# ExtensionConnector.net
KiCad netlist of a schematic drawn in Altium Designer
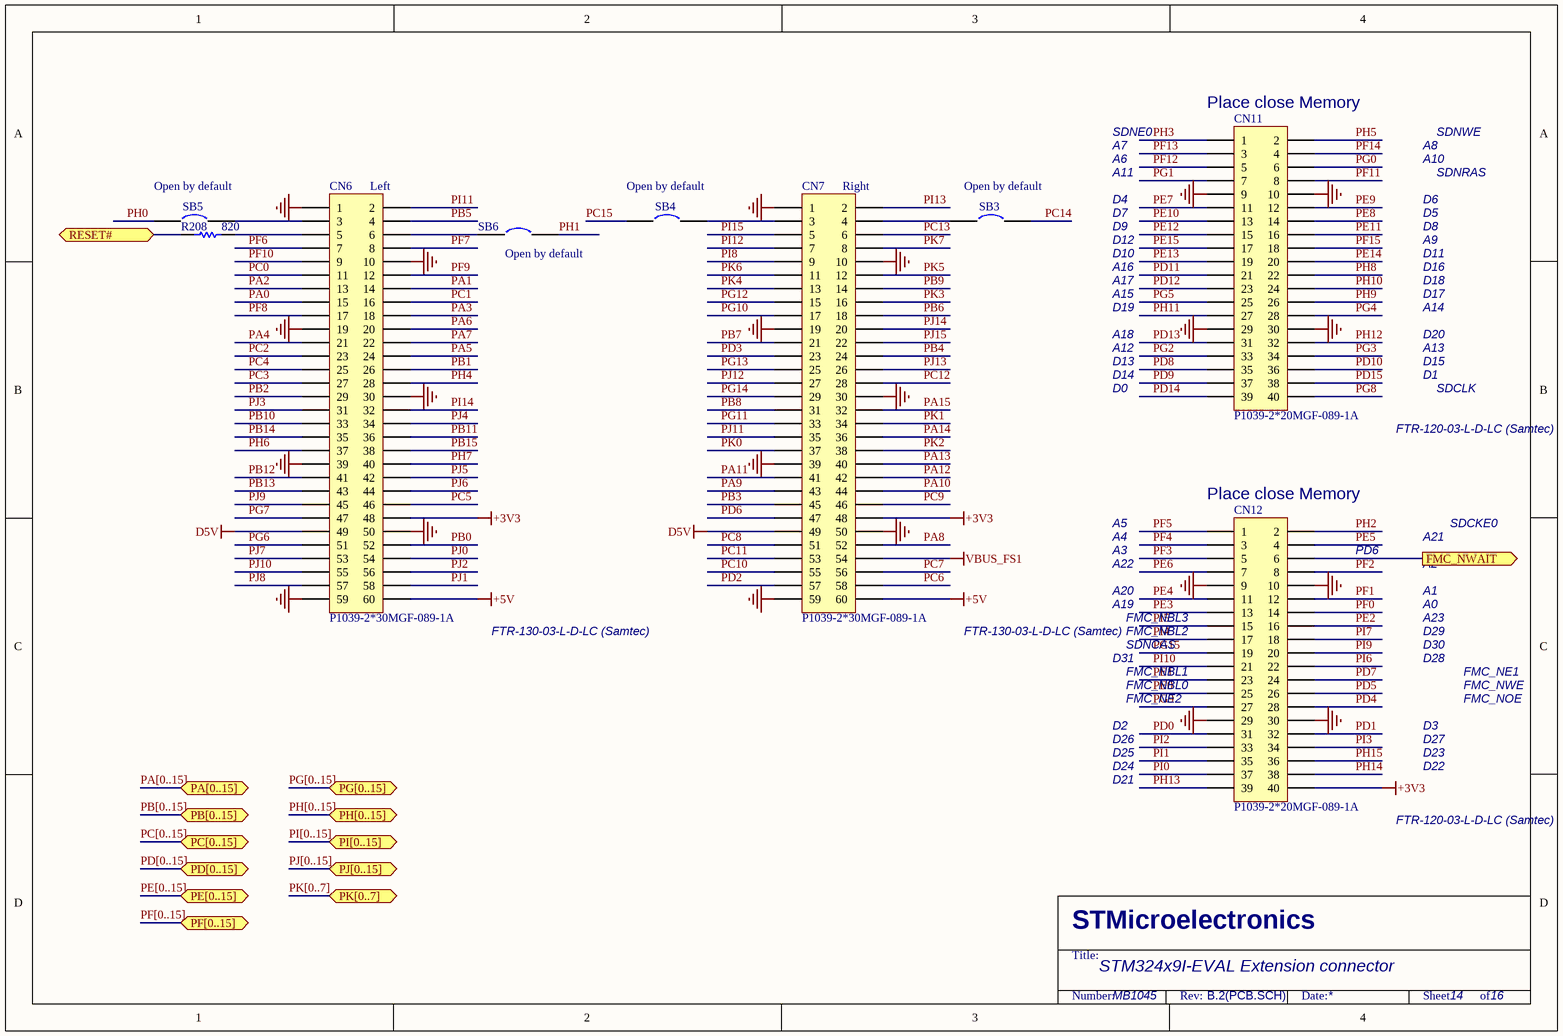
[diagram p0: ExtensionConnector.SchDoc]

(export (version "E")
  (design (tool "Eeschema 10.0.6"))
  (components
    (comp (ref "CN6")
      (value "P1039-2*30MGF-089-1A")
      (footprint "FTR-130-53-L-D-LC")
      (description "Header, 40-Pin, Dual row")
      (fields (field (name "PUBLISHER") "Altium Limited"))
      (libsource (lib "mb1045") (part "FTR-130-53-L-D-LC"))
    )
    (comp (ref "CN7")
      (value "P1039-2*30MGF-089-1A")
      (footprint "FTR-130-53-L-D-LC")
      (description "Header, 40-Pin, Dual row")
      (fields (field (name "PUBLISHER") "Altium Limited"))
      (libsource (lib "mb1045") (part "FTR-130-53-L-D-LC"))
    )
    (comp (ref "CN11")
      (value "P1039-2*20MGF-089-1A")
      (footprint "FTR-120-53-L-D-LC")
      (description "Header, 20-Pin, Dual row")
      (fields (field (name "PUBLISHER") "Altium Limited"))
      (libsource (lib "mb1045") (part "FTR-120-53-L-D-LC"))
    )
    (comp (ref "CN12")
      (value "P1039-2*20MGF-089-1A")
      (footprint "FTR-120-53-L-D-LC")
      (description "Header, 20-Pin, Dual row")
      (fields (field (name "PUBLISHER") "Altium Limited"))
      (libsource (lib "mb1045") (part "FTR-120-53-L-D-LC"))
    )
    (comp (ref "R208")
      (value "820")
      (footprint "0603R")
      (description "Resistor")
      (fields (field (name "PUBLISHER") "Altium Limited"))
      (libsource (lib "Miscellaneous Devices") (part "res1"))
    )
    (comp (ref "SB3")
      (value "~")
      (footprint "JP2_SMD")
      (description "Circuit Breaker")
      (fields (field (name "PUBLISHER") "Altium Limited"))
      (libsource (lib "Miscellaneous Devices") (part "Circuit Breaker"))
    )
    (comp (ref "SB4")
      (value "~")
      (footprint "JP2_SMD")
      (description "Circuit Breaker")
      (fields (field (name "PUBLISHER") "Altium Limited"))
      (libsource (lib "") (part "Circuit Breaker_1"))
    )
    (comp (ref "SB5")
      (value "~")
      (footprint "JP2_SMD")
      (description "Circuit Breaker")
      (fields (field (name "PUBLISHER") "Altium Limited"))
      (libsource (lib "") (part "Circuit Breaker_1"))
    )
    (comp (ref "SB6")
      (value "~")
      (footprint "JP2_SMD")
      (description "Circuit Breaker")
      (fields (field (name "PUBLISHER") "Altium Limited"))
      (libsource (lib "Miscellaneous Devices") (part "Circuit Breaker"))
    )
  )
  (nets
    (net (code "1") (name "+3V3") (class "Default")
      (node (ref "CN12") (pin "40") (pinfunction "40_40") (pintype "passive"))
      (node (ref "CN6") (pin "48") (pinfunction "48_48") (pintype "passive"))
      (node (ref "CN7") (pin "48") (pinfunction "48_48") (pintype "passive"))
    )
    (net (code "2") (name "+5V") (class "Default")
      (node (ref "CN6") (pin "60") (pinfunction "60_60") (pintype "passive"))
      (node (ref "CN7") (pin "60") (pinfunction "60_60") (pintype "passive"))
    )
    (net (code "3") (name "/FMC_NWAIT") (class "Default")
      (node (ref "CN12") (pin "6") (pinfunction "6_6") (pintype "passive"))
    )
    (net (code "4") (name "/PA0") (class "Default")
      (node (ref "CN6") (pin "15") (pinfunction "15_15") (pintype "passive"))
    )
    (net (code "5") (name "/PA1") (class "Default")
      (node (ref "CN6") (pin "14") (pinfunction "14_14") (pintype "passive"))
    )
    (net (code "6") (name "/PA2") (class "Default")
      (node (ref "CN6") (pin "13") (pinfunction "13_13") (pintype "passive"))
    )
    (net (code "7") (name "/PA3") (class "Default")
      (node (ref "CN6") (pin "18") (pinfunction "18_18") (pintype "passive"))
    )
    (net (code "8") (name "/PA4") (class "Default")
      (node (ref "CN6") (pin "21") (pinfunction "21_21") (pintype "passive"))
    )
    (net (code "9") (name "/PA5") (class "Default")
      (node (ref "CN6") (pin "24") (pinfunction "24_24") (pintype "passive"))
    )
    (net (code "10") (name "/PA6") (class "Default")
      (node (ref "CN6") (pin "20") (pinfunction "20_20") (pintype "passive"))
    )
    (net (code "11") (name "/PA7") (class "Default")
      (node (ref "CN6") (pin "22") (pinfunction "22_22") (pintype "passive"))
    )
    (net (code "12") (name "/PA8") (class "Default")
      (node (ref "CN7") (pin "52") (pinfunction "52_52") (pintype "passive"))
    )
    (net (code "13") (name "/PA9") (class "Default")
      (node (ref "CN7") (pin "43") (pinfunction "43_43") (pintype "passive"))
    )
    (net (code "14") (name "/PA10") (class "Default")
      (node (ref "CN7") (pin "44") (pinfunction "44_44") (pintype "passive"))
    )
    (net (code "15") (name "/PA11") (class "Default")
      (node (ref "CN7") (pin "41") (pinfunction "41_41") (pintype "passive"))
    )
    (net (code "16") (name "/PA12") (class "Default")
      (node (ref "CN7") (pin "42") (pinfunction "42_42") (pintype "passive"))
    )
    (net (code "17") (name "/PA13") (class "Default")
      (node (ref "CN7") (pin "40") (pinfunction "40_40") (pintype "passive"))
    )
    (net (code "18") (name "/PA14") (class "Default")
      (node (ref "CN7") (pin "36") (pinfunction "36_36") (pintype "passive"))
    )
    (net (code "19") (name "/PA15") (class "Default")
      (node (ref "CN7") (pin "32") (pinfunction "32_32") (pintype "passive"))
    )
    (net (code "21") (name "/PB0") (class "Default")
      (node (ref "CN6") (pin "52") (pinfunction "52_52") (pintype "passive"))
    )
    (net (code "22") (name "/PB1") (class "Default")
      (node (ref "CN6") (pin "26") (pinfunction "26_26") (pintype "passive"))
    )
    (net (code "23") (name "/PB2") (class "Default")
      (node (ref "CN6") (pin "29") (pinfunction "29_29") (pintype "passive"))
    )
    (net (code "24") (name "/PB3") (class "Default")
      (node (ref "CN7") (pin "45") (pinfunction "45_45") (pintype "passive"))
    )
    (net (code "25") (name "/PB4") (class "Default")
      (node (ref "CN7") (pin "24") (pinfunction "24_24") (pintype "passive"))
    )
    (net (code "26") (name "/PB5") (class "Default")
      (node (ref "CN6") (pin "4") (pinfunction "4_4") (pintype "passive"))
    )
    (net (code "27") (name "/PB6") (class "Default")
      (node (ref "CN7") (pin "18") (pinfunction "18_18") (pintype "passive"))
    )
    (net (code "28") (name "/PB7") (class "Default")
      (node (ref "CN7") (pin "21") (pinfunction "21_21") (pintype "passive"))
    )
    (net (code "29") (name "/PB8") (class "Default")
      (node (ref "CN7") (pin "31") (pinfunction "31_31") (pintype "passive"))
    )
    (net (code "30") (name "/PB9") (class "Default")
      (node (ref "CN7") (pin "14") (pinfunction "14_14") (pintype "passive"))
    )
    (net (code "31") (name "/PB10") (class "Default")
      (node (ref "CN6") (pin "33") (pinfunction "33_33") (pintype "passive"))
    )
    (net (code "32") (name "/PB11") (class "Default")
      (node (ref "CN6") (pin "36") (pinfunction "36_36") (pintype "passive"))
    )
    (net (code "33") (name "/PB12") (class "Default")
      (node (ref "CN6") (pin "41") (pinfunction "41_41") (pintype "passive"))
    )
    (net (code "34") (name "/PB13") (class "Default")
      (node (ref "CN6") (pin "43") (pinfunction "43_43") (pintype "passive"))
    )
    (net (code "35") (name "/PB14") (class "Default")
      (node (ref "CN6") (pin "35") (pinfunction "35_35") (pintype "passive"))
    )
    (net (code "36") (name "/PB15") (class "Default")
      (node (ref "CN6") (pin "38") (pinfunction "38_38") (pintype "passive"))
    )
    (net (code "38") (name "/PC0") (class "Default")
      (node (ref "CN6") (pin "11") (pinfunction "11_11") (pintype "passive"))
    )
    (net (code "39") (name "/PC1") (class "Default")
      (node (ref "CN6") (pin "16") (pinfunction "16_16") (pintype "passive"))
    )
    (net (code "40") (name "/PC2") (class "Default")
      (node (ref "CN6") (pin "23") (pinfunction "23_23") (pintype "passive"))
    )
    (net (code "41") (name "/PC3") (class "Default")
      (node (ref "CN6") (pin "27") (pinfunction "27_27") (pintype "passive"))
    )
    (net (code "42") (name "/PC4") (class "Default")
      (node (ref "CN6") (pin "25") (pinfunction "25_25") (pintype "passive"))
    )
    (net (code "43") (name "/PC5") (class "Default")
      (node (ref "CN6") (pin "46") (pinfunction "46_46") (pintype "passive"))
    )
    (net (code "44") (name "/PC6") (class "Default")
      (node (ref "CN7") (pin "58") (pinfunction "58_58") (pintype "passive"))
    )
    (net (code "45") (name "/PC7") (class "Default")
      (node (ref "CN7") (pin "56") (pinfunction "56_56") (pintype "passive"))
    )
    (net (code "46") (name "/PC8") (class "Default")
      (node (ref "CN7") (pin "51") (pinfunction "51_51") (pintype "passive"))
    )
    (net (code "47") (name "/PC9") (class "Default")
      (node (ref "CN7") (pin "46") (pinfunction "46_46") (pintype "passive"))
    )
    (net (code "48") (name "/PC10") (class "Default")
      (node (ref "CN7") (pin "55") (pinfunction "55_55") (pintype "passive"))
    )
    (net (code "49") (name "/PC11") (class "Default")
      (node (ref "CN7") (pin "53") (pinfunction "53_53") (pintype "passive"))
    )
    (net (code "50") (name "/PC12") (class "Default")
      (node (ref "CN7") (pin "28") (pinfunction "28_28") (pintype "passive"))
    )
    (net (code "51") (name "/PC13") (class "Default")
      (node (ref "CN7") (pin "6") (pinfunction "6_6") (pintype "passive"))
    )
    (net (code "52") (name "/PC14") (class "Default")
      (node (ref "SB3") (pin "1") (pinfunction "1_1") (pintype "passive"))
    )
    (net (code "53") (name "/PC15") (class "Default")
      (node (ref "SB4") (pin "1") (pinfunction "1_1") (pintype "passive"))
    )
    (net (code "55") (name "/PD0") (class "Default")
      (node (ref "CN12") (pin "31") (pinfunction "31_31") (pintype "passive"))
    )
    (net (code "56") (name "/PD1") (class "Default")
      (node (ref "CN12") (pin "32") (pinfunction "32_32") (pintype "passive"))
    )
    (net (code "57") (name "/PD2") (class "Default")
      (node (ref "CN7") (pin "57") (pinfunction "57_57") (pintype "passive"))
    )
    (net (code "58") (name "/PD3") (class "Default")
      (node (ref "CN7") (pin "23") (pinfunction "23_23") (pintype "passive"))
    )
    (net (code "59") (name "/PD4") (class "Default")
      (node (ref "CN12") (pin "28") (pinfunction "28_28") (pintype "passive"))
    )
    (net (code "60") (name "/PD5") (class "Default")
      (node (ref "CN12") (pin "26") (pinfunction "26_26") (pintype "passive"))
    )
    (net (code "61") (name "/PD6") (class "Default")
      (node (ref "CN7") (pin "47") (pinfunction "47_47") (pintype "passive"))
    )
    (net (code "62") (name "/PD7") (class "Default")
      (node (ref "CN12") (pin "24") (pinfunction "24_24") (pintype "passive"))
    )
    (net (code "63") (name "/PD8") (class "Default")
      (node (ref "CN11") (pin "35") (pinfunction "35_35") (pintype "passive"))
    )
    (net (code "64") (name "/PD9") (class "Default")
      (node (ref "CN11") (pin "37") (pinfunction "37_37") (pintype "passive"))
    )
    (net (code "65") (name "/PD10") (class "Default")
      (node (ref "CN11") (pin "36") (pinfunction "36_36") (pintype "passive"))
    )
    (net (code "66") (name "/PD11") (class "Default")
      (node (ref "CN11") (pin "21") (pinfunction "21_21") (pintype "passive"))
    )
    (net (code "67") (name "/PD12") (class "Default")
      (node (ref "CN11") (pin "23") (pinfunction "23_23") (pintype "passive"))
    )
    (net (code "68") (name "/PD13") (class "Default")
      (node (ref "CN11") (pin "31") (pinfunction "31_31") (pintype "passive"))
    )
    (net (code "69") (name "/PD14") (class "Default")
      (node (ref "CN11") (pin "39") (pinfunction "39_39") (pintype "passive"))
    )
    (net (code "70") (name "/PD15") (class "Default")
      (node (ref "CN11") (pin "38") (pinfunction "38_38") (pintype "passive"))
    )
    (net (code "72") (name "/PE0") (class "Default")
      (node (ref "CN12") (pin "25") (pinfunction "25_25") (pintype "passive"))
    )
    (net (code "73") (name "/PE1") (class "Default")
      (node (ref "CN12") (pin "23") (pinfunction "23_23") (pintype "passive"))
    )
    (net (code "74") (name "/PE2") (class "Default")
      (node (ref "CN12") (pin "16") (pinfunction "16_16") (pintype "passive"))
    )
    (net (code "75") (name "/PE3") (class "Default")
      (node (ref "CN12") (pin "13") (pinfunction "13_13") (pintype "passive"))
    )
    (net (code "76") (name "/PE4") (class "Default")
      (node (ref "CN12") (pin "11") (pinfunction "11_11") (pintype "passive"))
    )
    (net (code "77") (name "/PE5") (class "Default")
      (node (ref "CN12") (pin "4") (pinfunction "4_4") (pintype "passive"))
    )
    (net (code "78") (name "/PE6") (class "Default")
      (node (ref "CN12") (pin "7") (pinfunction "7_7") (pintype "passive"))
    )
    (net (code "79") (name "/PE7") (class "Default")
      (node (ref "CN11") (pin "11") (pinfunction "11_11") (pintype "passive"))
    )
    (net (code "80") (name "/PE8") (class "Default")
      (node (ref "CN11") (pin "14") (pinfunction "14_14") (pintype "passive"))
    )
    (net (code "81") (name "/PE9") (class "Default")
      (node (ref "CN11") (pin "12") (pinfunction "12_12") (pintype "passive"))
    )
    (net (code "82") (name "/PE10") (class "Default")
      (node (ref "CN11") (pin "13") (pinfunction "13_13") (pintype "passive"))
    )
    (net (code "83") (name "/PE11") (class "Default")
      (node (ref "CN11") (pin "16") (pinfunction "16_16") (pintype "passive"))
    )
    (net (code "84") (name "/PE12") (class "Default")
      (node (ref "CN11") (pin "15") (pinfunction "15_15") (pintype "passive"))
    )
    (net (code "85") (name "/PE13") (class "Default")
      (node (ref "CN11") (pin "19") (pinfunction "19_19") (pintype "passive"))
    )
    (net (code "86") (name "/PE14") (class "Default")
      (node (ref "CN11") (pin "20") (pinfunction "20_20") (pintype "passive"))
    )
    (net (code "87") (name "/PE15") (class "Default")
      (node (ref "CN11") (pin "17") (pinfunction "17_17") (pintype "passive"))
    )
    (net (code "89") (name "/PF0") (class "Default")
      (node (ref "CN12") (pin "14") (pinfunction "14_14") (pintype "passive"))
    )
    (net (code "90") (name "/PF1") (class "Default")
      (node (ref "CN12") (pin "12") (pinfunction "12_12") (pintype "passive"))
    )
    (net (code "91") (name "/PF2") (class "Default")
      (node (ref "CN12") (pin "8") (pinfunction "8_8") (pintype "passive"))
    )
    (net (code "92") (name "/PF3") (class "Default")
      (node (ref "CN12") (pin "5") (pinfunction "5_5") (pintype "passive"))
    )
    (net (code "93") (name "/PF4") (class "Default")
      (node (ref "CN12") (pin "3") (pinfunction "3_3") (pintype "passive"))
    )
    (net (code "94") (name "/PF5") (class "Default")
      (node (ref "CN12") (pin "1") (pinfunction "1_1") (pintype "passive"))
    )
    (net (code "95") (name "/PF6") (class "Default")
      (node (ref "CN6") (pin "7") (pinfunction "7_7") (pintype "passive"))
    )
    (net (code "96") (name "/PF7") (class "Default")
      (node (ref "CN6") (pin "8") (pinfunction "8_8") (pintype "passive"))
    )
    (net (code "97") (name "/PF8") (class "Default")
      (node (ref "CN6") (pin "17") (pinfunction "17_17") (pintype "passive"))
    )
    (net (code "98") (name "/PF9") (class "Default")
      (node (ref "CN6") (pin "12") (pinfunction "12_12") (pintype "passive"))
    )
    (net (code "99") (name "/PF10") (class "Default")
      (node (ref "CN6") (pin "9") (pinfunction "9_9") (pintype "passive"))
    )
    (net (code "100") (name "/PF11") (class "Default")
      (node (ref "CN11") (pin "8") (pinfunction "8_8") (pintype "passive"))
    )
    (net (code "101") (name "/PF12") (class "Default")
      (node (ref "CN11") (pin "5") (pinfunction "5_5") (pintype "passive"))
    )
    (net (code "102") (name "/PF13") (class "Default")
      (node (ref "CN11") (pin "3") (pinfunction "3_3") (pintype "passive"))
    )
    (net (code "103") (name "/PF14") (class "Default")
      (node (ref "CN11") (pin "4") (pinfunction "4_4") (pintype "passive"))
    )
    (net (code "104") (name "/PF15") (class "Default")
      (node (ref "CN11") (pin "18") (pinfunction "18_18") (pintype "passive"))
    )
    (net (code "106") (name "/PG0") (class "Default")
      (node (ref "CN11") (pin "6") (pinfunction "6_6") (pintype "passive"))
    )
    (net (code "107") (name "/PG1") (class "Default")
      (node (ref "CN11") (pin "7") (pinfunction "7_7") (pintype "passive"))
    )
    (net (code "108") (name "/PG2") (class "Default")
      (node (ref "CN11") (pin "33") (pinfunction "33_33") (pintype "passive"))
    )
    (net (code "109") (name "/PG3") (class "Default")
      (node (ref "CN11") (pin "34") (pinfunction "34_34") (pintype "passive"))
    )
    (net (code "110") (name "/PG4") (class "Default")
      (node (ref "CN11") (pin "28") (pinfunction "28_28") (pintype "passive"))
    )
    (net (code "111") (name "/PG5") (class "Default")
      (node (ref "CN11") (pin "25") (pinfunction "25_25") (pintype "passive"))
    )
    (net (code "112") (name "/PG6") (class "Default")
      (node (ref "CN6") (pin "51") (pinfunction "51_51") (pintype "passive"))
    )
    (net (code "113") (name "/PG7") (class "Default")
      (node (ref "CN6") (pin "47") (pinfunction "47_47") (pintype "passive"))
    )
    (net (code "114") (name "/PG8") (class "Default")
      (node (ref "CN11") (pin "40") (pinfunction "40_40") (pintype "passive"))
    )
    (net (code "115") (name "/PG9") (class "Default")
      (node (ref "CN12") (pin "27") (pinfunction "27_27") (pintype "passive"))
    )
    (net (code "116") (name "/PG10") (class "Default")
      (node (ref "CN7") (pin "17") (pinfunction "17_17") (pintype "passive"))
    )
    (net (code "117") (name "/PG11") (class "Default")
      (node (ref "CN7") (pin "33") (pinfunction "33_33") (pintype "passive"))
    )
    (net (code "118") (name "/PG12") (class "Default")
      (node (ref "CN7") (pin "15") (pinfunction "15_15") (pintype "passive"))
    )
    (net (code "119") (name "/PG13") (class "Default")
      (node (ref "CN7") (pin "25") (pinfunction "25_25") (pintype "passive"))
    )
    (net (code "120") (name "/PG14") (class "Default")
      (node (ref "CN7") (pin "29") (pinfunction "29_29") (pintype "passive"))
    )
    (net (code "121") (name "/PG15") (class "Default")
      (node (ref "CN12") (pin "19") (pinfunction "19_19") (pintype "passive"))
    )
    (net (code "123") (name "/PH0") (class "Default")
      (node (ref "SB5") (pin "1") (pinfunction "1_1") (pintype "passive"))
    )
    (net (code "124") (name "/PH1") (class "Default")
      (node (ref "SB6") (pin "1") (pinfunction "1_1") (pintype "passive"))
    )
    (net (code "125") (name "/PH2") (class "Default")
      (node (ref "CN12") (pin "2") (pinfunction "2_2") (pintype "passive"))
    )
    (net (code "126") (name "/PH3") (class "Default")
      (node (ref "CN11") (pin "1") (pinfunction "1_1") (pintype "passive"))
    )
    (net (code "127") (name "/PH4") (class "Default")
      (node (ref "CN6") (pin "28") (pinfunction "28_28") (pintype "passive"))
    )
    (net (code "128") (name "/PH5") (class "Default")
      (node (ref "CN11") (pin "2") (pinfunction "2_2") (pintype "passive"))
    )
    (net (code "129") (name "/PH6") (class "Default")
      (node (ref "CN6") (pin "37") (pinfunction "37_37") (pintype "passive"))
    )
    (net (code "130") (name "/PH7") (class "Default")
      (node (ref "CN6") (pin "40") (pinfunction "40_40") (pintype "passive"))
    )
    (net (code "131") (name "/PH8") (class "Default")
      (node (ref "CN11") (pin "22") (pinfunction "22_22") (pintype "passive"))
    )
    (net (code "132") (name "/PH9") (class "Default")
      (node (ref "CN11") (pin "26") (pinfunction "26_26") (pintype "passive"))
    )
    (net (code "133") (name "/PH10") (class "Default")
      (node (ref "CN11") (pin "24") (pinfunction "24_24") (pintype "passive"))
    )
    (net (code "134") (name "/PH11") (class "Default")
      (node (ref "CN11") (pin "27") (pinfunction "27_27") (pintype "passive"))
    )
    (net (code "135") (name "/PH12") (class "Default")
      (node (ref "CN11") (pin "32") (pinfunction "32_32") (pintype "passive"))
    )
    (net (code "136") (name "/PH13") (class "Default")
      (node (ref "CN12") (pin "39") (pinfunction "39_39") (pintype "passive"))
    )
    (net (code "137") (name "/PH14") (class "Default")
      (node (ref "CN12") (pin "38") (pinfunction "38_38") (pintype "passive"))
    )
    (net (code "138") (name "/PH15") (class "Default")
      (node (ref "CN12") (pin "36") (pinfunction "36_36") (pintype "passive"))
    )
    (net (code "140") (name "/PI0") (class "Default")
      (node (ref "CN12") (pin "37") (pinfunction "37_37") (pintype "passive"))
    )
    (net (code "141") (name "/PI1") (class "Default")
      (node (ref "CN12") (pin "35") (pinfunction "35_35") (pintype "passive"))
    )
    (net (code "142") (name "/PI2") (class "Default")
      (node (ref "CN12") (pin "33") (pinfunction "33_33") (pintype "passive"))
    )
    (net (code "143") (name "/PI3") (class "Default")
      (node (ref "CN12") (pin "34") (pinfunction "34_34") (pintype "passive"))
    )
    (net (code "144") (name "/PI4") (class "Default")
      (node (ref "CN12") (pin "17") (pinfunction "17_17") (pintype "passive"))
    )
    (net (code "145") (name "/PI5") (class "Default")
      (node (ref "CN12") (pin "15") (pinfunction "15_15") (pintype "passive"))
    )
    (net (code "146") (name "/PI6") (class "Default")
      (node (ref "CN12") (pin "22") (pinfunction "22_22") (pintype "passive"))
    )
    (net (code "147") (name "/PI7") (class "Default")
      (node (ref "CN12") (pin "18") (pinfunction "18_18") (pintype "passive"))
    )
    (net (code "148") (name "/PI8") (class "Default")
      (node (ref "CN7") (pin "9") (pinfunction "9_9") (pintype "passive"))
    )
    (net (code "149") (name "/PI9") (class "Default")
      (node (ref "CN12") (pin "20") (pinfunction "20_20") (pintype "passive"))
    )
    (net (code "150") (name "/PI10") (class "Default")
      (node (ref "CN12") (pin "21") (pinfunction "21_21") (pintype "passive"))
    )
    (net (code "151") (name "/PI11") (class "Default")
      (node (ref "CN6") (pin "2") (pinfunction "2_2") (pintype "passive"))
    )
    (net (code "152") (name "/PI12") (class "Default")
      (node (ref "CN7") (pin "7") (pinfunction "7_7") (pintype "passive"))
    )
    (net (code "153") (name "/PI13") (class "Default")
      (node (ref "CN7") (pin "2") (pinfunction "2_2") (pintype "passive"))
    )
    (net (code "154") (name "/PI14") (class "Default")
      (node (ref "CN6") (pin "32") (pinfunction "32_32") (pintype "passive"))
    )
    (net (code "155") (name "/PI15") (class "Default")
      (node (ref "CN7") (pin "5") (pinfunction "5_5") (pintype "passive"))
    )
    (net (code "157") (name "/PJ0") (class "Default")
      (node (ref "CN6") (pin "54") (pinfunction "54_54") (pintype "passive"))
    )
    (net (code "158") (name "/PJ1") (class "Default")
      (node (ref "CN6") (pin "58") (pinfunction "58_58") (pintype "passive"))
    )
    (net (code "159") (name "/PJ2") (class "Default")
      (node (ref "CN6") (pin "56") (pinfunction "56_56") (pintype "passive"))
    )
    (net (code "160") (name "/PJ3") (class "Default")
      (node (ref "CN6") (pin "31") (pinfunction "31_31") (pintype "passive"))
    )
    (net (code "161") (name "/PJ4") (class "Default")
      (node (ref "CN6") (pin "34") (pinfunction "34_34") (pintype "passive"))
    )
    (net (code "162") (name "/PJ5") (class "Default")
      (node (ref "CN6") (pin "42") (pinfunction "42_42") (pintype "passive"))
    )
    (net (code "163") (name "/PJ6") (class "Default")
      (node (ref "CN6") (pin "44") (pinfunction "44_44") (pintype "passive"))
    )
    (net (code "164") (name "/PJ7") (class "Default")
      (node (ref "CN6") (pin "53") (pinfunction "53_53") (pintype "passive"))
    )
    (net (code "165") (name "/PJ8") (class "Default")
      (node (ref "CN6") (pin "57") (pinfunction "57_57") (pintype "passive"))
    )
    (net (code "166") (name "/PJ9") (class "Default")
      (node (ref "CN6") (pin "45") (pinfunction "45_45") (pintype "passive"))
    )
    (net (code "167") (name "/PJ10") (class "Default")
      (node (ref "CN6") (pin "55") (pinfunction "55_55") (pintype "passive"))
    )
    (net (code "168") (name "/PJ11") (class "Default")
      (node (ref "CN7") (pin "35") (pinfunction "35_35") (pintype "passive"))
    )
    (net (code "169") (name "/PJ12") (class "Default")
      (node (ref "CN7") (pin "27") (pinfunction "27_27") (pintype "passive"))
    )
    (net (code "170") (name "/PJ13") (class "Default")
      (node (ref "CN7") (pin "26") (pinfunction "26_26") (pintype "passive"))
    )
    (net (code "171") (name "/PJ14") (class "Default")
      (node (ref "CN7") (pin "20") (pinfunction "20_20") (pintype "passive"))
    )
    (net (code "172") (name "/PJ15") (class "Default")
      (node (ref "CN7") (pin "22") (pinfunction "22_22") (pintype "passive"))
    )
    (net (code "174") (name "/PK0") (class "Default")
      (node (ref "CN7") (pin "37") (pinfunction "37_37") (pintype "passive"))
    )
    (net (code "175") (name "/PK1") (class "Default")
      (node (ref "CN7") (pin "34") (pinfunction "34_34") (pintype "passive"))
    )
    (net (code "176") (name "/PK2") (class "Default")
      (node (ref "CN7") (pin "38") (pinfunction "38_38") (pintype "passive"))
    )
    (net (code "177") (name "/PK3") (class "Default")
      (node (ref "CN7") (pin "16") (pinfunction "16_16") (pintype "passive"))
    )
    (net (code "178") (name "/PK4") (class "Default")
      (node (ref "CN7") (pin "13") (pinfunction "13_13") (pintype "passive"))
    )
    (net (code "179") (name "/PK5") (class "Default")
      (node (ref "CN7") (pin "12") (pinfunction "12_12") (pintype "passive"))
    )
    (net (code "180") (name "/PK6") (class "Default")
      (node (ref "CN7") (pin "11") (pinfunction "11_11") (pintype "passive"))
    )
    (net (code "181") (name "/PK7") (class "Default")
      (node (ref "CN7") (pin "8") (pinfunction "8_8") (pintype "passive"))
    )
    (net (code "183") (name "/RESET#") (class "Default")
      (node (ref "R208") (pin "1") (pinfunction "1_1") (pintype "passive"))
    )
    (net (code "184") (name "D5V") (class "Default")
      (node (ref "CN6") (pin "49") (pinfunction "49_49") (pintype "passive"))
      (node (ref "CN7") (pin "49") (pinfunction "49_49") (pintype "passive"))
    )
    (net (code "185") (name "GND") (class "Default")
      (node (ref "CN11") (pin "10") (pinfunction "10_10") (pintype "passive"))
      (node (ref "CN11") (pin "29") (pinfunction "29_29") (pintype "passive"))
      (node (ref "CN11") (pin "30") (pinfunction "30_30") (pintype "passive"))
      (node (ref "CN11") (pin "9") (pinfunction "9_9") (pintype "passive"))
      (node (ref "CN12") (pin "10") (pinfunction "10_10") (pintype "passive"))
      (node (ref "CN12") (pin "29") (pinfunction "29_29") (pintype "passive"))
      (node (ref "CN12") (pin "30") (pinfunction "30_30") (pintype "passive"))
      (node (ref "CN12") (pin "9") (pinfunction "9_9") (pintype "passive"))
      (node (ref "CN6") (pin "1") (pinfunction "1_1") (pintype "passive"))
      (node (ref "CN6") (pin "10") (pinfunction "10_10") (pintype "passive"))
      (node (ref "CN6") (pin "19") (pinfunction "19_19") (pintype "passive"))
      (node (ref "CN6") (pin "30") (pinfunction "30_30") (pintype "passive"))
      (node (ref "CN6") (pin "39") (pinfunction "39_39") (pintype "passive"))
      (node (ref "CN6") (pin "50") (pinfunction "50_50") (pintype "passive"))
      (node (ref "CN6") (pin "59") (pinfunction "59_59") (pintype "passive"))
      (node (ref "CN7") (pin "1") (pinfunction "1_1") (pintype "passive"))
      (node (ref "CN7") (pin "10") (pinfunction "10_10") (pintype "passive"))
      (node (ref "CN7") (pin "19") (pinfunction "19_19") (pintype "passive"))
      (node (ref "CN7") (pin "30") (pinfunction "30_30") (pintype "passive"))
      (node (ref "CN7") (pin "39") (pinfunction "39_39") (pintype "passive"))
      (node (ref "CN7") (pin "50") (pinfunction "50_50") (pintype "passive"))
      (node (ref "CN7") (pin "59") (pinfunction "59_59") (pintype "passive"))
    )
    (net (code "186") (name "Net-(CN6-Pad3)") (class "Default")
      (node (ref "CN6") (pin "3") (pinfunction "3_3") (pintype "passive"))
      (node (ref "SB5") (pin "2") (pinfunction "2_2") (pintype "passive"))
    )
    (net (code "187") (name "Net-(CN6-Pad5)") (class "Default")
      (node (ref "CN6") (pin "5") (pinfunction "5_5") (pintype "passive"))
      (node (ref "R208") (pin "2") (pinfunction "2_2") (pintype "passive"))
    )
    (net (code "188") (name "Net-(CN6-Pad6)") (class "Default")
      (node (ref "CN6") (pin "6") (pinfunction "6_6") (pintype "passive"))
      (node (ref "SB6") (pin "2") (pinfunction "2_2") (pintype "passive"))
    )
    (net (code "189") (name "Net-(CN7-Pad3)") (class "Default")
      (node (ref "CN7") (pin "3") (pinfunction "3_3") (pintype "passive"))
      (node (ref "SB4") (pin "2") (pinfunction "2_2") (pintype "passive"))
    )
    (net (code "190") (name "Net-(CN7-Pad4)") (class "Default")
      (node (ref "CN7") (pin "4") (pinfunction "4_4") (pintype "passive"))
      (node (ref "SB3") (pin "2") (pinfunction "2_2") (pintype "passive"))
    )
    (net (code "191") (name "VBUS_FS1") (class "Default")
      (node (ref "CN7") (pin "54") (pinfunction "54_54") (pintype "passive"))
    )
  )
)
